# PPD42.net
KiCad netlist of a schematic drawn in EAGLE
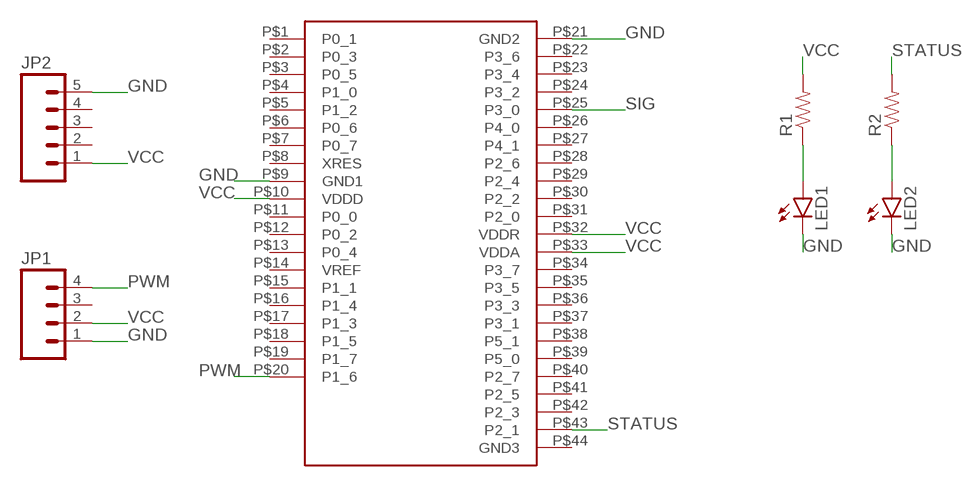
[diagram p0: schematic, sheet 1]

(export (version "E")
  (design (tool "Eeschema 10.0.6"))
  (components
    (comp (ref "JP1")
      (value "M04LONGPADS")
      (footprint "eagle-import:1X04_LONGPADS")
      (libsource (lib "eagle-import") (part "M04LONGPADS"))
    )
    (comp (ref "JP2")
      (value "M05PTH_LONGPADS")
      (footprint "eagle-import:1X05_LONGPADS")
      (libsource (lib "eagle-import") (part "M05PTH_LONGPADS"))
    )
    (comp (ref "LED1")
      (value "LED3MM")
      (footprint "eagle-import:LED3MM")
      (libsource (lib "eagle-import") (part "LED3MM"))
    )
    (comp (ref "LED2")
      (value "LED3MM")
      (footprint "eagle-import:LED3MM")
      (libsource (lib "eagle-import") (part "LED3MM"))
    )
    (comp (ref "R1")
      (value "RESISTORPTH-1/4W")
      (footprint "eagle-import:AXIAL-0.4")
      (libsource (lib "eagle-import") (part "RESISTORPTH-1/4W"))
    )
    (comp (ref "R2")
      (value "RESISTORPTH-1/4W")
      (footprint "eagle-import:AXIAL-0.4")
      (libsource (lib "eagle-import") (part "RESISTORPTH-1/4W"))
    )
    (comp (ref "U$1")
      (value "CYBLE_MODULE")
      (footprint "eagle-import:CYBLE_MODULE")
      (libsource (lib "eagle-import") (part "CYBLE_MODULE"))
    )
  )
  (nets
    (net (code "1") (name "/GND") (class "Default")
      (node (ref "JP1") (pin "1") (pinfunction "1_1") (pintype "passive"))
      (node (ref "JP2") (pin "5") (pinfunction "5_5") (pintype "passive"))
      (node (ref "LED1") (pin "K") (pinfunction "C_K") (pintype "passive"))
      (node (ref "LED2") (pin "K") (pinfunction "C_K") (pintype "passive"))
      (node (ref "U$1") (pin "P$21") (pinfunction "GND2_P$21") (pintype "bidirectional"))
      (node (ref "U$1") (pin "P$9") (pinfunction "GND1_P$9") (pintype "bidirectional"))
    )
    (net (code "2") (name "/PWM") (class "Default")
      (node (ref "JP1") (pin "4") (pinfunction "4_4") (pintype "passive"))
      (node (ref "U$1") (pin "P$20") (pinfunction "P1_6_P$20") (pintype "bidirectional"))
    )
    (net (code "3") (name "/SIG") (class "Default")
      (node (ref "U$1") (pin "P$25") (pinfunction "P3_0_P$25") (pintype "bidirectional"))
    )
    (net (code "4") (name "/STATUS") (class "Default")
      (node (ref "R2") (pin "P$2") (pinfunction "2_P$2") (pintype "passive"))
      (node (ref "U$1") (pin "P$43") (pinfunction "P2_1_P$43") (pintype "bidirectional"))
    )
    (net (code "5") (name "/VCC") (class "Default")
      (node (ref "JP1") (pin "2") (pinfunction "2_2") (pintype "passive"))
      (node (ref "JP2") (pin "1") (pinfunction "1_1") (pintype "passive"))
      (node (ref "R1") (pin "P$2") (pinfunction "2_P$2") (pintype "passive"))
      (node (ref "U$1") (pin "P$10") (pinfunction "VDDD_P$10") (pintype "bidirectional"))
      (node (ref "U$1") (pin "P$32") (pinfunction "VDDR_P$32") (pintype "bidirectional"))
      (node (ref "U$1") (pin "P$33") (pinfunction "VDDA_P$33") (pintype "bidirectional"))
    )
    (net (code "6") (name "Net-(R1-1)") (class "Default")
      (node (ref "LED1") (pin "A") (pinfunction "A_A") (pintype "passive"))
      (node (ref "R1") (pin "P$1") (pinfunction "1_P$1") (pintype "passive"))
    )
    (net (code "7") (name "Net-(R2-1)") (class "Default")
      (node (ref "LED2") (pin "A") (pinfunction "A_A") (pintype "passive"))
      (node (ref "R2") (pin "P$1") (pinfunction "1_P$1") (pintype "passive"))
    )
    (net (code "8") (name "unconnected-(JP1-Pad3)") (class "Default")
      (node (ref "JP1") (pin "3") (pinfunction "3_3") (pintype "passive"))
    )
    (net (code "9") (name "unconnected-(JP2-Pad2)") (class "Default")
      (node (ref "JP2") (pin "2") (pinfunction "2_2") (pintype "passive"))
    )
    (net (code "10") (name "unconnected-(JP2-Pad3)") (class "Default")
      (node (ref "JP2") (pin "3") (pinfunction "3_3") (pintype "passive"))
    )
    (net (code "11") (name "unconnected-(JP2-Pad4)") (class "Default")
      (node (ref "JP2") (pin "4") (pinfunction "4_4") (pintype "passive"))
    )
    (net (code "12") (name "unconnected-(U$1-GND3-PadP$44)") (class "Default")
      (node (ref "U$1") (pin "P$44") (pinfunction "GND3_P$44") (pintype "bidirectional"))
    )
    (net (code "13") (name "unconnected-(U$1-P0_0-PadP$11)") (class "Default")
      (node (ref "U$1") (pin "P$11") (pinfunction "P0_0_P$11") (pintype "bidirectional"))
    )
    (net (code "14") (name "unconnected-(U$1-P0_1-PadP$1)") (class "Default")
      (node (ref "U$1") (pin "P$1") (pinfunction "P0_1_P$1") (pintype "bidirectional"))
    )
    (net (code "15") (name "unconnected-(U$1-P0_2-PadP$12)") (class "Default")
      (node (ref "U$1") (pin "P$12") (pinfunction "P0_2_P$12") (pintype "bidirectional"))
    )
    (net (code "16") (name "unconnected-(U$1-P0_3-PadP$2)") (class "Default")
      (node (ref "U$1") (pin "P$2") (pinfunction "P0_3_P$2") (pintype "bidirectional"))
    )
    (net (code "17") (name "unconnected-(U$1-P0_4-PadP$13)") (class "Default")
      (node (ref "U$1") (pin "P$13") (pinfunction "P0_4_P$13") (pintype "bidirectional"))
    )
    (net (code "18") (name "unconnected-(U$1-P0_5-PadP$3)") (class "Default")
      (node (ref "U$1") (pin "P$3") (pinfunction "P0_5_P$3") (pintype "bidirectional"))
    )
    (net (code "19") (name "unconnected-(U$1-P0_6-PadP$6)") (class "Default")
      (node (ref "U$1") (pin "P$6") (pinfunction "P0_6_P$6") (pintype "bidirectional"))
    )
    (net (code "20") (name "unconnected-(U$1-P0_7-PadP$7)") (class "Default")
      (node (ref "U$1") (pin "P$7") (pinfunction "P0_7_P$7") (pintype "bidirectional"))
    )
    (net (code "21") (name "unconnected-(U$1-P1_0-PadP$4)") (class "Default")
      (node (ref "U$1") (pin "P$4") (pinfunction "P1_0_P$4") (pintype "bidirectional"))
    )
    (net (code "22") (name "unconnected-(U$1-P1_1-PadP$15)") (class "Default")
      (node (ref "U$1") (pin "P$15") (pinfunction "P1_1_P$15") (pintype "bidirectional"))
    )
    (net (code "23") (name "unconnected-(U$1-P1_2-PadP$5)") (class "Default")
      (node (ref "U$1") (pin "P$5") (pinfunction "P1_2_P$5") (pintype "bidirectional"))
    )
    (net (code "24") (name "unconnected-(U$1-P1_3-PadP$17)") (class "Default")
      (node (ref "U$1") (pin "P$17") (pinfunction "P1_3_P$17") (pintype "bidirectional"))
    )
    (net (code "25") (name "unconnected-(U$1-P1_4-PadP$16)") (class "Default")
      (node (ref "U$1") (pin "P$16") (pinfunction "P1_4_P$16") (pintype "bidirectional"))
    )
    (net (code "26") (name "unconnected-(U$1-P1_5-PadP$18)") (class "Default")
      (node (ref "U$1") (pin "P$18") (pinfunction "P1_5_P$18") (pintype "bidirectional"))
    )
    (net (code "27") (name "unconnected-(U$1-P1_7-PadP$19)") (class "Default")
      (node (ref "U$1") (pin "P$19") (pinfunction "P1_7_P$19") (pintype "bidirectional"))
    )
    (net (code "28") (name "unconnected-(U$1-P2_0-PadP$31)") (class "Default")
      (node (ref "U$1") (pin "P$31") (pinfunction "P2_0_P$31") (pintype "bidirectional"))
    )
    (net (code "29") (name "unconnected-(U$1-P2_2-PadP$30)") (class "Default")
      (node (ref "U$1") (pin "P$30") (pinfunction "P2_2_P$30") (pintype "bidirectional"))
    )
    (net (code "30") (name "unconnected-(U$1-P2_3-PadP$42)") (class "Default")
      (node (ref "U$1") (pin "P$42") (pinfunction "P2_3_P$42") (pintype "bidirectional"))
    )
    (net (code "31") (name "unconnected-(U$1-P2_4-PadP$29)") (class "Default")
      (node (ref "U$1") (pin "P$29") (pinfunction "P2_4_P$29") (pintype "bidirectional"))
    )
    (net (code "32") (name "unconnected-(U$1-P2_5-PadP$41)") (class "Default")
      (node (ref "U$1") (pin "P$41") (pinfunction "P2_5_P$41") (pintype "bidirectional"))
    )
    (net (code "33") (name "unconnected-(U$1-P2_6-PadP$28)") (class "Default")
      (node (ref "U$1") (pin "P$28") (pinfunction "P2_6_P$28") (pintype "bidirectional"))
    )
    (net (code "34") (name "unconnected-(U$1-P2_7-PadP$40)") (class "Default")
      (node (ref "U$1") (pin "P$40") (pinfunction "P2_7_P$40") (pintype "bidirectional"))
    )
    (net (code "35") (name "unconnected-(U$1-P3_1-PadP$37)") (class "Default")
      (node (ref "U$1") (pin "P$37") (pinfunction "P3_1_P$37") (pintype "bidirectional"))
    )
    (net (code "36") (name "unconnected-(U$1-P3_2-PadP$24)") (class "Default")
      (node (ref "U$1") (pin "P$24") (pinfunction "P3_2_P$24") (pintype "bidirectional"))
    )
    (net (code "37") (name "unconnected-(U$1-P3_3-PadP$36)") (class "Default")
      (node (ref "U$1") (pin "P$36") (pinfunction "P3_3_P$36") (pintype "bidirectional"))
    )
    (net (code "38") (name "unconnected-(U$1-P3_4-PadP$23)") (class "Default")
      (node (ref "U$1") (pin "P$23") (pinfunction "P3_4_P$23") (pintype "bidirectional"))
    )
    (net (code "39") (name "unconnected-(U$1-P3_5-PadP$35)") (class "Default")
      (node (ref "U$1") (pin "P$35") (pinfunction "P3_5_P$35") (pintype "bidirectional"))
    )
    (net (code "40") (name "unconnected-(U$1-P3_6-PadP$22)") (class "Default")
      (node (ref "U$1") (pin "P$22") (pinfunction "P3_6_P$22") (pintype "bidirectional"))
    )
    (net (code "41") (name "unconnected-(U$1-P3_7-PadP$34)") (class "Default")
      (node (ref "U$1") (pin "P$34") (pinfunction "P3_7_P$34") (pintype "bidirectional"))
    )
    (net (code "42") (name "unconnected-(U$1-P4_0-PadP$26)") (class "Default")
      (node (ref "U$1") (pin "P$26") (pinfunction "P4_0_P$26") (pintype "bidirectional"))
    )
    (net (code "43") (name "unconnected-(U$1-P4_1-PadP$27)") (class "Default")
      (node (ref "U$1") (pin "P$27") (pinfunction "P4_1_P$27") (pintype "bidirectional"))
    )
    (net (code "44") (name "unconnected-(U$1-P5_0-PadP$39)") (class "Default")
      (node (ref "U$1") (pin "P$39") (pinfunction "P5_0_P$39") (pintype "bidirectional"))
    )
    (net (code "45") (name "unconnected-(U$1-P5_1-PadP$38)") (class "Default")
      (node (ref "U$1") (pin "P$38") (pinfunction "P5_1_P$38") (pintype "bidirectional"))
    )
    (net (code "46") (name "unconnected-(U$1-VREF-PadP$14)") (class "Default")
      (node (ref "U$1") (pin "P$14") (pinfunction "VREF_P$14") (pintype "bidirectional"))
    )
    (net (code "47") (name "unconnected-(U$1-XRES-PadP$8)") (class "Default")
      (node (ref "U$1") (pin "P$8") (pinfunction "XRES_P$8") (pintype "bidirectional"))
    )
  )
)
